# 4_Strain_Gauge_Board.net
KiCad netlist of a schematic drawn in EAGLE
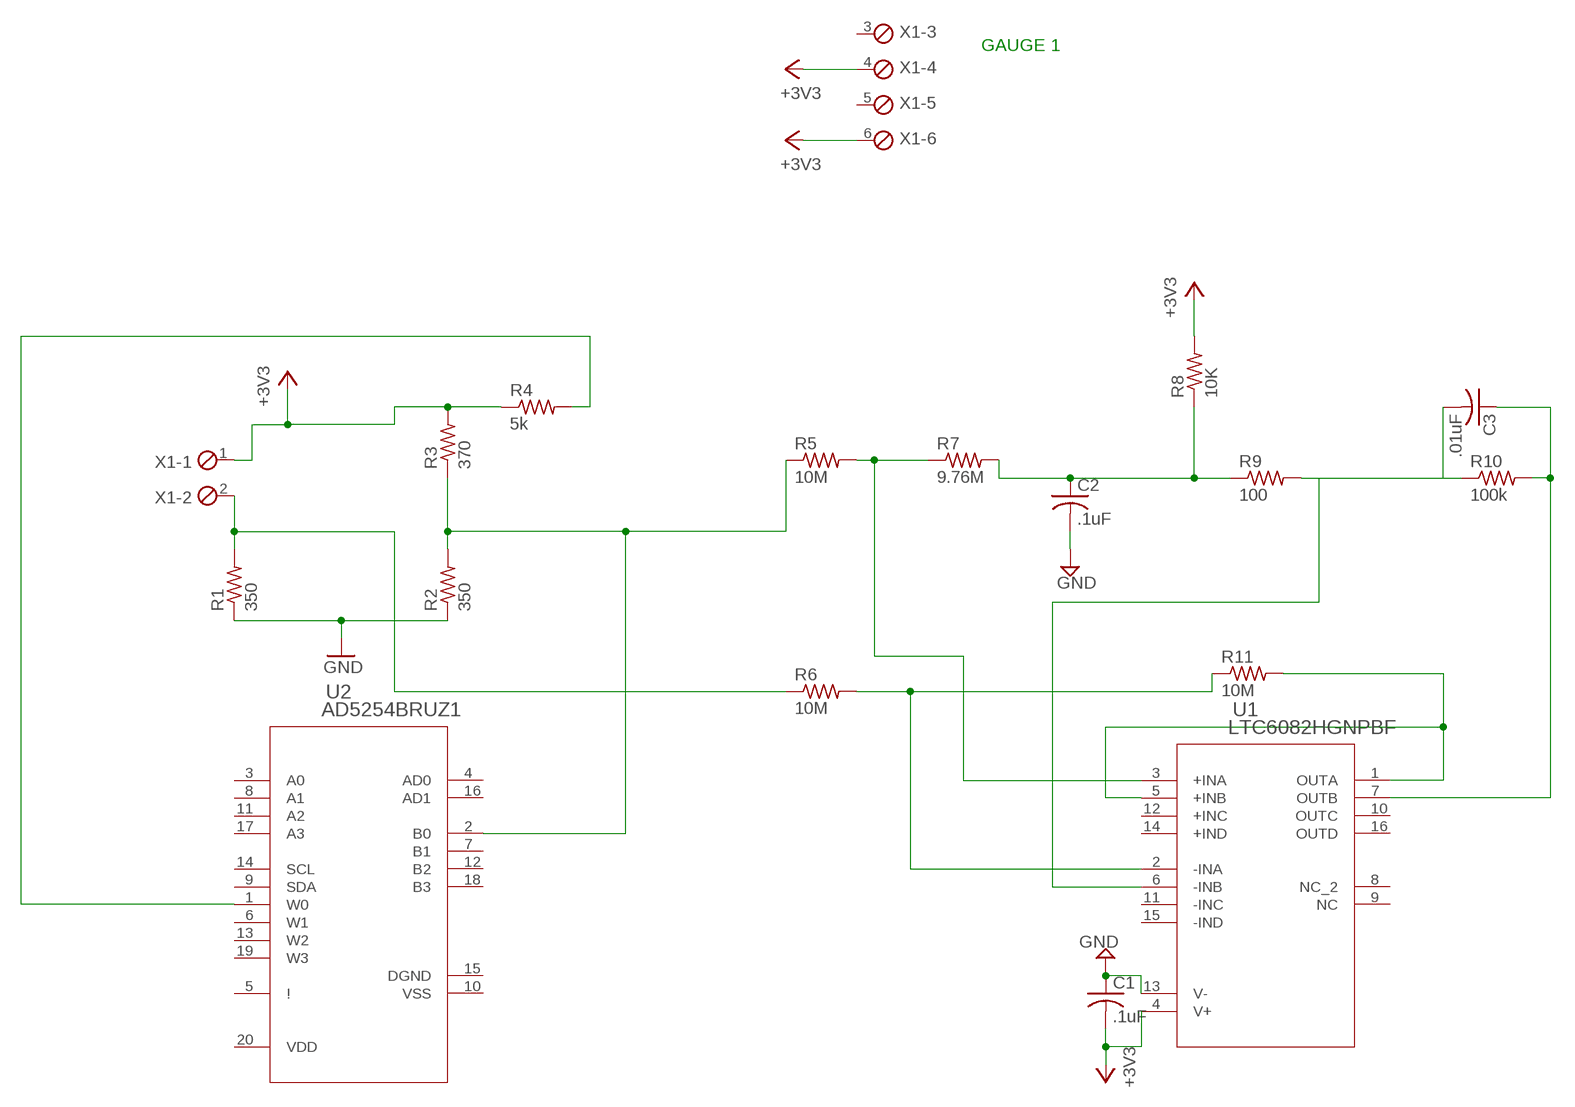
[diagram p0: schematic, sheet 1]

(export (version "E")
  (design (tool "Eeschema 10.0.6"))
  (components
    (comp (ref "C1")
      (value ".1uF")
      (footprint "eagle-import:C1206K")
      (libsource (lib "eagle-import") (part "C-USC1206K"))
    )
    (comp (ref "C2")
      (value ".1uF")
      (footprint "eagle-import:C1206K")
      (libsource (lib "eagle-import") (part "C-USC1206K"))
    )
    (comp (ref "C3")
      (value ".01uF")
      (footprint "eagle-import:C1206K")
      (libsource (lib "eagle-import") (part "C-USC1206K"))
    )
    (comp (ref "R1")
      (value "350")
      (footprint "eagle-import:M1206")
      (libsource (lib "eagle-import") (part "R-US_M1206"))
    )
    (comp (ref "R2")
      (value "350")
      (footprint "eagle-import:M1206")
      (libsource (lib "eagle-import") (part "R-US_M1206"))
    )
    (comp (ref "R3")
      (value "370")
      (footprint "eagle-import:M1206")
      (libsource (lib "eagle-import") (part "R-US_M1206"))
    )
    (comp (ref "R4")
      (value "5k")
      (footprint "eagle-import:M1206")
      (libsource (lib "eagle-import") (part "R-US_M1206"))
    )
    (comp (ref "R5")
      (value "10M")
      (footprint "eagle-import:M1206")
      (libsource (lib "eagle-import") (part "R-US_M1206"))
    )
    (comp (ref "R6")
      (value "10M")
      (footprint "eagle-import:M1206")
      (libsource (lib "eagle-import") (part "R-US_M1206"))
    )
    (comp (ref "R7")
      (value "9.76M")
      (footprint "eagle-import:M1206")
      (libsource (lib "eagle-import") (part "R-US_M1206"))
    )
    (comp (ref "R8")
      (value "10K")
      (footprint "eagle-import:M1206")
      (libsource (lib "eagle-import") (part "R-US_M1206"))
    )
    (comp (ref "R9")
      (value "100")
      (footprint "eagle-import:M1206")
      (libsource (lib "eagle-import") (part "R-US_M1206"))
    )
    (comp (ref "R10")
      (value "100k")
      (footprint "eagle-import:M1206")
      (libsource (lib "eagle-import") (part "R-US_M1206"))
    )
    (comp (ref "R11")
      (value "10M")
      (footprint "eagle-import:M1206")
      (libsource (lib "eagle-import") (part "R-US_M1206"))
    )
    (comp (ref "U1")
      (value "LTC6082HGNPBF")
      (footprint "eagle-import:SSOP-16_GN")
      (fields (field (name "MANUFACTURER_PART_NUMBER") "LTC6082HGN#PBF"))
      (libsource (lib "eagle-import") (part "LTC6082HGNPBF"))
    )
    (comp (ref "U2")
      (value "AD5254BRUZ1")
      (footprint "eagle-import:RU_20")
      (libsource (lib "eagle-import") (part "AD5254BRUZ1"))
    )
    (comp (ref "X1")
      (value "MPT6")
      (footprint "eagle-import:6POL254")
      (libsource (lib "eagle-import") (part "MPT6"))
    )
  )
  (nets
    (net (code "1") (name "+3V3") (class "Default")
      (node (ref "C1") (pin "2") (pinfunction "2_2") (pintype "passive"))
      (node (ref "R3") (pin "2") (pinfunction "2_2") (pintype "passive"))
      (node (ref "R4") (pin "1") (pinfunction "1_1") (pintype "passive"))
      (node (ref "R8") (pin "2") (pinfunction "2_2") (pintype "passive"))
      (node (ref "U1") (pin "4") (pinfunction "V+_4") (pintype "power_in"))
      (node (ref "X1") (pin "1") (pinfunction "1_1") (pintype "passive"))
      (node (ref "X1") (pin "4") (pinfunction "1_4") (pintype "passive"))
      (node (ref "X1") (pin "6") (pinfunction "1_6") (pintype "passive"))
    )
    (net (code "2") (name "/VDD") (class "Default")
      (node (ref "U2") (pin "20") (pinfunction "VDD_20") (pintype "power_in"))
    )
    (net (code "3") (name "/VSS") (class "Default")
      (node (ref "U2") (pin "10") (pinfunction "VSS_10") (pintype "power_in"))
    )
    (net (code "4") (name "GND") (class "Default")
      (node (ref "C1") (pin "1") (pinfunction "1_1") (pintype "passive"))
      (node (ref "C2") (pin "2") (pinfunction "2_2") (pintype "passive"))
      (node (ref "R1") (pin "1") (pinfunction "1_1") (pintype "passive"))
      (node (ref "R2") (pin "1") (pinfunction "1_1") (pintype "passive"))
      (node (ref "U1") (pin "13") (pinfunction "V-_13") (pintype "power_in"))
    )
    (net (code "5") (name "Net-(C2-Pad1)") (class "Default")
      (node (ref "C2") (pin "1") (pinfunction "1_1") (pintype "passive"))
      (node (ref "R7") (pin "2") (pinfunction "2_2") (pintype "passive"))
      (node (ref "R8") (pin "1") (pinfunction "1_1") (pintype "passive"))
      (node (ref "R9") (pin "1") (pinfunction "1_1") (pintype "passive"))
    )
    (net (code "6") (name "Net-(U1-+INA)") (class "Default")
      (node (ref "R5") (pin "2") (pinfunction "2_2") (pintype "passive"))
      (node (ref "R7") (pin "1") (pinfunction "1_1") (pintype "passive"))
      (node (ref "U1") (pin "3") (pinfunction "+INA_3") (pintype "input"))
    )
    (net (code "7") (name "Net-(U1-+INB)") (class "Default")
      (node (ref "R11") (pin "2") (pinfunction "2_2") (pintype "passive"))
      (node (ref "U1") (pin "1") (pinfunction "OUTA_1") (pintype "output"))
      (node (ref "U1") (pin "5") (pinfunction "+INB_5") (pintype "input"))
    )
    (net (code "8") (name "Net-(U1--INA)") (class "Default")
      (node (ref "R11") (pin "1") (pinfunction "1_1") (pintype "passive"))
      (node (ref "R6") (pin "2") (pinfunction "2_2") (pintype "passive"))
      (node (ref "U1") (pin "2") (pinfunction "-INA_2") (pintype "input"))
    )
    (net (code "9") (name "Net-(U1--INB)") (class "Default")
      (node (ref "C3") (pin "2") (pinfunction "2_2") (pintype "passive"))
      (node (ref "R10") (pin "1") (pinfunction "1_1") (pintype "passive"))
      (node (ref "R9") (pin "2") (pinfunction "2_2") (pintype "passive"))
      (node (ref "U1") (pin "6") (pinfunction "-INB_6") (pintype "input"))
    )
    (net (code "10") (name "Net-(U1-OUTB)") (class "Default")
      (node (ref "C3") (pin "1") (pinfunction "1_1") (pintype "passive"))
      (node (ref "R10") (pin "2") (pinfunction "2_2") (pintype "passive"))
      (node (ref "U1") (pin "7") (pinfunction "OUTB_7") (pintype "output"))
    )
    (net (code "11") (name "Net-(U2-B0)") (class "Default")
      (node (ref "R2") (pin "2") (pinfunction "2_2") (pintype "passive"))
      (node (ref "R3") (pin "1") (pinfunction "1_1") (pintype "passive"))
      (node (ref "R5") (pin "1") (pinfunction "1_1") (pintype "passive"))
      (node (ref "U2") (pin "2") (pinfunction "B0_2") (pintype "passive"))
    )
    (net (code "12") (name "Net-(U2-W0)") (class "Default")
      (node (ref "R4") (pin "2") (pinfunction "2_2") (pintype "passive"))
      (node (ref "U2") (pin "1") (pinfunction "W0_1") (pintype "passive"))
    )
    (net (code "13") (name "Net-(X1B-1)") (class "Default")
      (node (ref "R1") (pin "2") (pinfunction "2_2") (pintype "passive"))
      (node (ref "R6") (pin "1") (pinfunction "1_1") (pintype "passive"))
      (node (ref "X1") (pin "2") (pinfunction "1_2") (pintype "passive"))
    )
    (net (code "14") (name "unconnected-(U1-+INC-Pad12)") (class "Default")
      (node (ref "U1") (pin "12") (pinfunction "+INC_12") (pintype "input"))
    )
    (net (code "15") (name "unconnected-(U1-+IND-Pad14)") (class "Default")
      (node (ref "U1") (pin "14") (pinfunction "+IND_14") (pintype "input"))
    )
    (net (code "16") (name "unconnected-(U1--INC-Pad11)") (class "Default")
      (node (ref "U1") (pin "11") (pinfunction "-INC_11") (pintype "input"))
    )
    (net (code "17") (name "unconnected-(U1--IND-Pad15)") (class "Default")
      (node (ref "U1") (pin "15") (pinfunction "-IND_15") (pintype "input"))
    )
    (net (code "18") (name "unconnected-(U1-NC-Pad9)") (class "Default")
      (node (ref "U1") (pin "9") (pinfunction "NC_9") (pintype "no_connect"))
    )
    (net (code "19") (name "unconnected-(U1-NC_2-Pad8)") (class "Default")
      (node (ref "U1") (pin "8") (pinfunction "NC_2_8") (pintype "no_connect"))
    )
    (net (code "20") (name "unconnected-(U1-OUTC-Pad10)") (class "Default")
      (node (ref "U1") (pin "10") (pinfunction "OUTC_10") (pintype "output"))
    )
    (net (code "21") (name "unconnected-(U1-OUTD-Pad16)") (class "Default")
      (node (ref "U1") (pin "16") (pinfunction "OUTD_16") (pintype "output"))
    )
    (net (code "22") (name "unconnected-(U2-A0-Pad3)") (class "Default")
      (node (ref "U2") (pin "3") (pinfunction "A0_3") (pintype "passive"))
    )
    (net (code "23") (name "unconnected-(U2-A1-Pad8)") (class "Default")
      (node (ref "U2") (pin "8") (pinfunction "A1_8") (pintype "passive"))
    )
    (net (code "24") (name "unconnected-(U2-A2-Pad11)") (class "Default")
      (node (ref "U2") (pin "11") (pinfunction "A2_11") (pintype "passive"))
    )
    (net (code "25") (name "unconnected-(U2-A3-Pad17)") (class "Default")
      (node (ref "U2") (pin "17") (pinfunction "A3_17") (pintype "passive"))
    )
    (net (code "26") (name "unconnected-(U2-AD0-Pad4)") (class "Default")
      (node (ref "U2") (pin "4") (pinfunction "AD0_4") (pintype "passive"))
    )
    (net (code "27") (name "unconnected-(U2-AD1-Pad16)") (class "Default")
      (node (ref "U2") (pin "16") (pinfunction "AD1_16") (pintype "passive"))
    )
    (net (code "28") (name "unconnected-(U2-B1-Pad7)") (class "Default")
      (node (ref "U2") (pin "7") (pinfunction "B1_7") (pintype "passive"))
    )
    (net (code "29") (name "unconnected-(U2-B2-Pad12)") (class "Default")
      (node (ref "U2") (pin "12") (pinfunction "B2_12") (pintype "passive"))
    )
    (net (code "30") (name "unconnected-(U2-B3-Pad18)") (class "Default")
      (node (ref "U2") (pin "18") (pinfunction "B3_18") (pintype "passive"))
    )
    (net (code "31") (name "unconnected-(U2-DGND-Pad15)") (class "Default")
      (node (ref "U2") (pin "15") (pinfunction "DGND_15") (pintype "passive"))
    )
    (net (code "32") (name "unconnected-(U2-SCL-Pad14)") (class "Default")
      (node (ref "U2") (pin "14") (pinfunction "SCL_14") (pintype "passive"))
    )
    (net (code "33") (name "unconnected-(U2-SDA-Pad9)") (class "Default")
      (node (ref "U2") (pin "9") (pinfunction "SDA_9") (pintype "passive"))
    )
    (net (code "34") (name "unconnected-(U2-W1-Pad6)") (class "Default")
      (node (ref "U2") (pin "6") (pinfunction "W1_6") (pintype "passive"))
    )
    (net (code "35") (name "unconnected-(U2-W2-Pad13)") (class "Default")
      (node (ref "U2") (pin "13") (pinfunction "W2_13") (pintype "passive"))
    )
    (net (code "36") (name "unconnected-(U2-W3-Pad19)") (class "Default")
      (node (ref "U2") (pin "19") (pinfunction "W3_19") (pintype "passive"))
    )
    (net (code "37") (name "unconnected-(U2-~-Pad5)") (class "Default")
      (node (ref "U2") (pin "5") (pinfunction "~_5") (pintype "passive"))
    )
    (net (code "38") (name "unconnected-(X1C-1-Pad3)") (class "Default")
      (node (ref "X1") (pin "3") (pinfunction "1_3") (pintype "passive"))
    )
    (net (code "39") (name "unconnected-(X1E-1-Pad5)") (class "Default")
      (node (ref "X1") (pin "5") (pinfunction "1_5") (pintype "passive"))
    )
  )
)
